# S2C_IOs1V8.net
KiCad netlist of a schematic drawn in Altium Designer
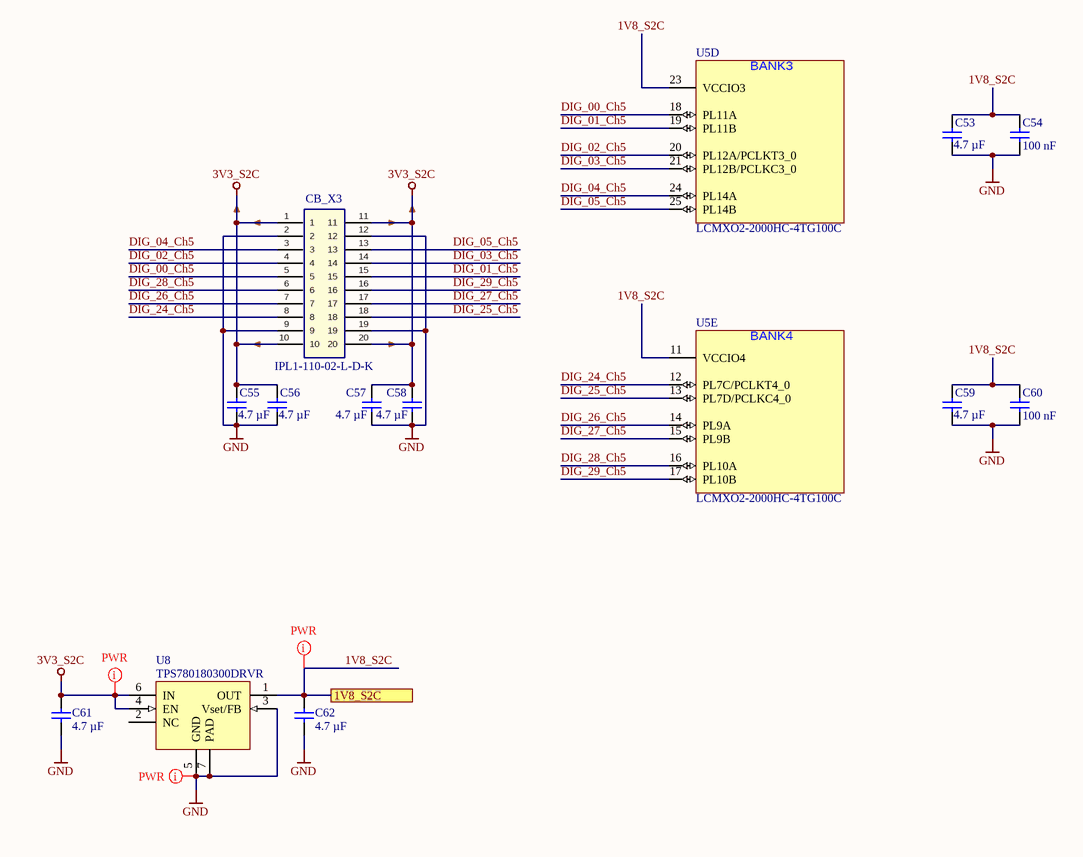
[diagram p0: S2C_IOs1V8.SchDoc]

(export (version "E")
  (design (tool "Eeschema 10.0.6"))
  (components
    (comp (ref "C53")
      (value "4.7 µF")
      (footprint "C_0603_TE")
      (description "Generic capacitor")
      (fields
        (field (name "MANUFACTURER PART NUMBER") "UZgen_C_0603_4.7uF_16V_X5R")
        (field (name "MANUFACTURER") "UZgen")
        (field (name "CREATED FROM") "MGeier")
      )
      (libsource (lib "user") (part "CAP-NP"))
    )
    (comp (ref "C54")
      (value "100 nF")
      (footprint "C_0603_TE")
      (description "Generic capacitor")
      (fields
        (field (name "TOLERANCE") "10 %")
        (field (name "VOLTAGE") "50 V")
        (field (name "CREATED FROM") "AGeiger")
      )
      (libsource (lib "user") (part "CAP-NP"))
    )
    (comp (ref "C55")
      (value "4.7 µF")
      (footprint "C_0603_TE")
      (description "Generic capacitor")
      (fields
        (field (name "MANUFACTURER PART NUMBER") "UZgen_C_0603_4.7uF_16V_X5R")
        (field (name "MANUFACTURER") "UZgen")
        (field (name "CREATED FROM") "MGeier")
      )
      (libsource (lib "user") (part "CAP-NP"))
    )
    (comp (ref "C56")
      (value "4.7 µF")
      (footprint "C_0603_TE")
      (description "Generic capacitor")
      (fields
        (field (name "MANUFACTURER PART NUMBER") "UZgen_C_0603_4.7uF_16V_X5R")
        (field (name "MANUFACTURER") "UZgen")
        (field (name "CREATED FROM") "MGeier")
      )
      (libsource (lib "user") (part "CAP-NP"))
    )
    (comp (ref "C57")
      (value "4.7 µF")
      (footprint "C_0603_TE")
      (description "Generic capacitor")
      (fields
        (field (name "MANUFACTURER PART NUMBER") "UZgen_C_0603_4.7uF_16V_X5R")
        (field (name "MANUFACTURER") "UZgen")
        (field (name "CREATED FROM") "MGeier")
      )
      (libsource (lib "user") (part "CAP-NP"))
    )
    (comp (ref "C58")
      (value "4.7 µF")
      (footprint "C_0603_TE")
      (description "Generic capacitor")
      (fields
        (field (name "MANUFACTURER PART NUMBER") "UZgen_C_0603_4.7uF_16V_X5R")
        (field (name "MANUFACTURER") "UZgen")
        (field (name "CREATED FROM") "MGeier")
      )
      (libsource (lib "user") (part "CAP-NP"))
    )
    (comp (ref "C59")
      (value "4.7 µF")
      (footprint "C_0603_TE")
      (description "Generic capacitor")
      (fields
        (field (name "MANUFACTURER PART NUMBER") "UZgen_C_0603_4.7uF_16V_X5R")
        (field (name "MANUFACTURER") "UZgen")
        (field (name "CREATED FROM") "MGeier")
      )
      (libsource (lib "user") (part "CAP-NP"))
    )
    (comp (ref "C60")
      (value "100 nF")
      (footprint "C_0603_TE")
      (description "Generic capacitor")
      (fields
        (field (name "TOLERANCE") "10 %")
        (field (name "VOLTAGE") "50 V")
        (field (name "CREATED FROM") "AGeiger")
      )
      (libsource (lib "user") (part "CAP-NP"))
    )
    (comp (ref "C61")
      (value "4.7 µF")
      (footprint "C_0603_TE")
      (description "Generic capacitor")
      (fields
        (field (name "MANUFACTURER PART NUMBER") "UZgen_C_0603_4.7uF_16V_X5R")
        (field (name "MANUFACTURER") "UZgen")
        (field (name "CREATED FROM") "MGeier")
      )
      (libsource (lib "user") (part "CAP-NP"))
    )
    (comp (ref "C62")
      (value "4.7 µF")
      (footprint "C_0603_TE")
      (description "Generic capacitor")
      (fields
        (field (name "MANUFACTURER PART NUMBER") "UZgen_C_0603_4.7uF_16V_X5R")
        (field (name "MANUFACTURER") "UZgen")
        (field (name "CREATED FROM") "MGeier")
      )
      (libsource (lib "user") (part "CAP-NP"))
    )
    (comp (ref "CB_X3")
      (value "IPL1-110-02-L-D-K")
      (footprint "IPL1-110-02-L-D-K")
      (description "2.54 mm Double Row Termin Assembly (SMD)")
      (fields
        (field (name "MANUFACTURER") "SAMTEC")
        (field (name "LCSC PART NUMBER") "C7544188")
        (field (name "CREATED FROM") "MGremer")
      )
      (libsource (lib "user") (part "IPL1-110-XX-X-D-X"))
    )
    (comp (ref "U5")
      (value "LCMXO2-2000HC-4TG100C")
      (footprint "QFP50P1600X1600X160-100N")
      (description "TQFP-100(14x14) Programmable Logic Device (CPLDs/FPGAs) ROHS")
      (fields
        (field (name "MANUFACTURER") "Lattice")
        (field (name "LCSC PART NUMBER") "C1521632")
        (field (name "CREATED FROM") "FRosner")
      )
      (libsource (lib "user") (part "LCMXO2-2000"))
    )
    (comp (ref "U8")
      (value "TPS780180300DRVR")
      (footprint "SON65P200X200X80-7N")
      (description "LDO Voltage Regulators 150mA,LDO Reg,Ultra Low Pwr")
      (fields
        (field (name "MANUFACTURER") "Texas Instruments")
        (field (name "LCSC PART NUMBER") "C2860011")
        (field (name "CREATED FROM") "FRosner")
      )
      (libsource (lib "user") (part "TPS780180300DRV"))
    )
  )
  (nets
    (net (code "1") (name "/1V8_S2C") (class "Default")
      (node (ref "C53") (pin "1") (pinfunction "1_1") (pintype "passive"))
      (node (ref "C54") (pin "2") (pinfunction "2_2") (pintype "passive"))
      (node (ref "C59") (pin "1") (pinfunction "1_1") (pintype "passive"))
      (node (ref "C60") (pin "2") (pinfunction "2_2") (pintype "passive"))
      (node (ref "C62") (pin "2") (pinfunction "2_2") (pintype "passive"))
      (node (ref "U5") (pin "11") (pinfunction "VCCIO4_11") (pintype "power_in"))
      (node (ref "U5") (pin "23") (pinfunction "VCCIO3_23") (pintype "power_in"))
      (node (ref "U8") (pin "1") (pinfunction "OUT_1") (pintype "passive"))
    )
    (net (code "2") (name "/DIG_00_Ch5") (class "Default")
      (node (ref "CB_X3") (pin "5") (pinfunction "5_5") (pintype "passive"))
      (node (ref "U5") (pin "18") (pinfunction "PL11A_18") (pintype "bidirectional"))
    )
    (net (code "3") (name "/DIG_01_Ch5") (class "Default")
      (node (ref "CB_X3") (pin "15") (pinfunction "15_15") (pintype "passive"))
      (node (ref "U5") (pin "19") (pinfunction "PL11B_19") (pintype "bidirectional"))
    )
    (net (code "4") (name "/DIG_02_Ch5") (class "Default")
      (node (ref "CB_X3") (pin "4") (pinfunction "4_4") (pintype "passive"))
      (node (ref "U5") (pin "20") (pinfunction "PL12A/PCLKT3_0_20") (pintype "bidirectional"))
    )
    (net (code "5") (name "/DIG_03_Ch5") (class "Default")
      (node (ref "CB_X3") (pin "14") (pinfunction "14_14") (pintype "passive"))
      (node (ref "U5") (pin "21") (pinfunction "PL12B/PCLKC3_0_21") (pintype "bidirectional"))
    )
    (net (code "6") (name "/DIG_04_Ch5") (class "Default")
      (node (ref "CB_X3") (pin "3") (pinfunction "3_3") (pintype "passive"))
      (node (ref "U5") (pin "24") (pinfunction "PL14A_24") (pintype "bidirectional"))
    )
    (net (code "7") (name "/DIG_05_Ch5") (class "Default")
      (node (ref "CB_X3") (pin "13") (pinfunction "13_13") (pintype "passive"))
      (node (ref "U5") (pin "25") (pinfunction "PL14B_25") (pintype "bidirectional"))
    )
    (net (code "8") (name "/DIG_24_Ch5") (class "Default")
      (node (ref "CB_X3") (pin "8") (pinfunction "8_8") (pintype "passive"))
      (node (ref "U5") (pin "12") (pinfunction "PL7C/PCLKT4_0_12") (pintype "bidirectional"))
    )
    (net (code "9") (name "/DIG_25_Ch5") (class "Default")
      (node (ref "CB_X3") (pin "18") (pinfunction "18_18") (pintype "passive"))
      (node (ref "U5") (pin "13") (pinfunction "PL7D/PCLKC4_0_13") (pintype "bidirectional"))
    )
    (net (code "10") (name "/DIG_26_Ch5") (class "Default")
      (node (ref "CB_X3") (pin "7") (pinfunction "7_7") (pintype "passive"))
      (node (ref "U5") (pin "14") (pinfunction "PL9A_14") (pintype "bidirectional"))
    )
    (net (code "11") (name "/DIG_27_Ch5") (class "Default")
      (node (ref "CB_X3") (pin "17") (pinfunction "17_17") (pintype "passive"))
      (node (ref "U5") (pin "15") (pinfunction "PL9B_15") (pintype "bidirectional"))
    )
    (net (code "12") (name "/DIG_28_Ch5") (class "Default")
      (node (ref "CB_X3") (pin "6") (pinfunction "6_6") (pintype "passive"))
      (node (ref "U5") (pin "16") (pinfunction "PL10A_16") (pintype "bidirectional"))
    )
    (net (code "13") (name "/DIG_29_Ch5") (class "Default")
      (node (ref "CB_X3") (pin "16") (pinfunction "16_16") (pintype "passive"))
      (node (ref "U5") (pin "17") (pinfunction "PL10B_17") (pintype "bidirectional"))
    )
    (net (code "14") (name "3V3_S2C") (class "Default")
      (node (ref "C55") (pin "1") (pinfunction "1_1") (pintype "passive"))
      (node (ref "C56") (pin "1") (pinfunction "1_1") (pintype "passive"))
      (node (ref "C57") (pin "1") (pinfunction "1_1") (pintype "passive"))
      (node (ref "C58") (pin "1") (pinfunction "1_1") (pintype "passive"))
      (node (ref "C61") (pin "2") (pinfunction "2_2") (pintype "passive"))
      (node (ref "CB_X3") (pin "1") (pinfunction "1_1") (pintype "passive"))
      (node (ref "CB_X3") (pin "10") (pinfunction "10_10") (pintype "passive"))
      (node (ref "CB_X3") (pin "11") (pinfunction "11_11") (pintype "passive"))
      (node (ref "CB_X3") (pin "20") (pinfunction "20_20") (pintype "passive"))
      (node (ref "U8") (pin "4") (pinfunction "EN_4") (pintype "input"))
      (node (ref "U8") (pin "6") (pinfunction "IN_6") (pintype "power_in"))
    )
    (net (code "15") (name "GND") (class "Default")
      (node (ref "C53") (pin "2") (pinfunction "2_2") (pintype "passive"))
      (node (ref "C54") (pin "1") (pinfunction "1_1") (pintype "passive"))
      (node (ref "C55") (pin "2") (pinfunction "2_2") (pintype "passive"))
      (node (ref "C56") (pin "2") (pinfunction "2_2") (pintype "passive"))
      (node (ref "C57") (pin "2") (pinfunction "2_2") (pintype "passive"))
      (node (ref "C58") (pin "2") (pinfunction "2_2") (pintype "passive"))
      (node (ref "C59") (pin "2") (pinfunction "2_2") (pintype "passive"))
      (node (ref "C60") (pin "1") (pinfunction "1_1") (pintype "passive"))
      (node (ref "C61") (pin "1") (pinfunction "1_1") (pintype "passive"))
      (node (ref "C62") (pin "1") (pinfunction "1_1") (pintype "passive"))
      (node (ref "CB_X3") (pin "12") (pinfunction "12_12") (pintype "passive"))
      (node (ref "CB_X3") (pin "19") (pinfunction "19_19") (pintype "passive"))
      (node (ref "CB_X3") (pin "2") (pinfunction "2_2") (pintype "passive"))
      (node (ref "CB_X3") (pin "9") (pinfunction "9_9") (pintype "passive"))
      (node (ref "U8") (pin "3") (pinfunction "Vset/FB_3") (pintype "input"))
      (node (ref "U8") (pin "5") (pinfunction "GND_5") (pintype "power_in"))
      (node (ref "U8") (pin "7") (pinfunction "PAD_7") (pintype "passive"))
    )
    (net (code "16") (name "unconnected-(U8-NC-Pad2)") (class "Default")
      (node (ref "U8") (pin "2") (pinfunction "NC_2") (pintype "passive"))
    )
  )
)
